# TD_0002-100_2.net
KiCad netlist of a schematic drawn in Altium Designer
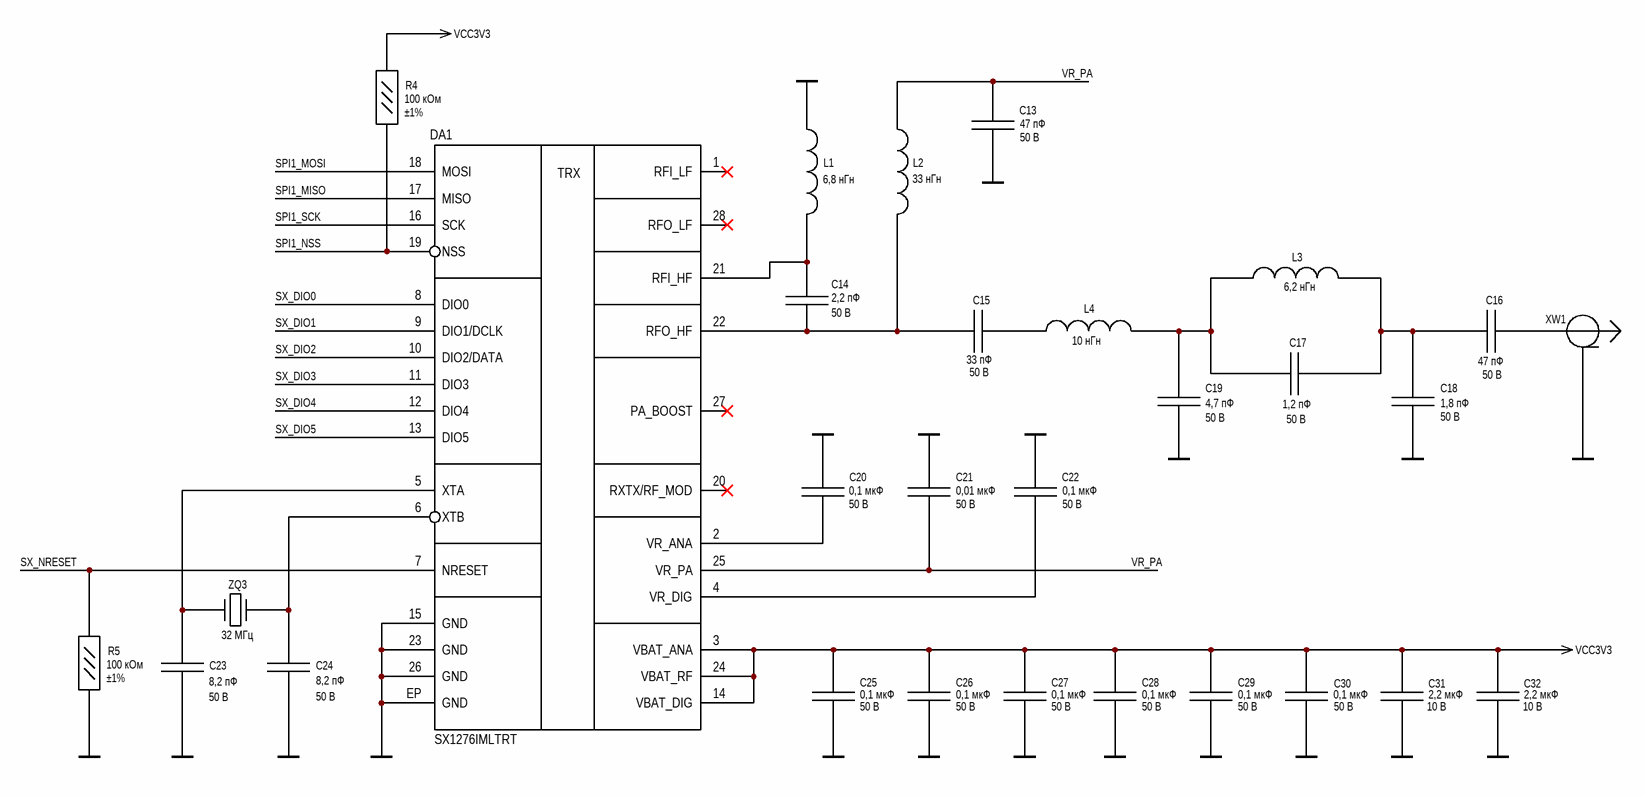
[diagram p0: TD.0002-100_2.SchDoc]

(export (version "E")
  (design (tool "Eeschema 10.0.6"))
  (components
    (comp (ref "C13")
      (value "47 пФ")
      (footprint "C_0402")
      (description "Chip Multilayer Ceramic Capacitor")
      (fields
        (field (name "PART NUMBER") "GRM1555C1H470GA01")
        (field (name "MANUFACTURER") "Murata")
        (field (name "VOLTAGE") "50 В")
      )
      (libsource (lib "Database_Libs") (part "Capacitor"))
    )
    (comp (ref "C14")
      (value "2,2 пФ")
      (footprint "C_0402")
      (description "Chip Multilayer Ceramic Capacitor")
      (fields
        (field (name "PART NUMBER") "GRM1555C1H2R2CA01")
        (field (name "MANUFACTURER") "Murata")
        (field (name "VOLTAGE") "50 В")
      )
      (libsource (lib "Database_Libs") (part "Capacitor"))
    )
    (comp (ref "C15")
      (value "33 пФ")
      (footprint "C_0402")
      (description "Chip Multilayer Ceramic Capacitor")
      (fields
        (field (name "PART NUMBER") "GRM1555C1H330GA01")
        (field (name "MANUFACTURER") "Murata")
        (field (name "VOLTAGE") "50 В")
      )
      (libsource (lib "Database_Libs") (part "Capacitor"))
    )
    (comp (ref "C16")
      (value "47 пФ")
      (footprint "C_0402")
      (description "Chip Multilayer Ceramic Capacitor")
      (fields
        (field (name "PART NUMBER") "GRM1555C1H470GA01")
        (field (name "MANUFACTURER") "Murata")
        (field (name "VOLTAGE") "50 В")
      )
      (libsource (lib "Database_Libs") (part "Capacitor"))
    )
    (comp (ref "C17")
      (value "1,2 пФ")
      (footprint "C_0402")
      (description "Chip Multilayer Ceramic Capacitor")
      (fields
        (field (name "PART NUMBER") "GRM1555C1H1R2CA01")
        (field (name "MANUFACTURER") "Murata")
        (field (name "VOLTAGE") "50 В")
      )
      (libsource (lib "Database_Libs") (part "Capacitor"))
    )
    (comp (ref "C18")
      (value "1,8 пФ")
      (footprint "C_0402")
      (description "Chip Multilayer Ceramic Capacitor")
      (fields
        (field (name "PART NUMBER") "GRM1555C1H1R8CA01")
        (field (name "MANUFACTURER") "Murata")
        (field (name "VOLTAGE") "50 В")
      )
      (libsource (lib "Database_Libs") (part "Capacitor"))
    )
    (comp (ref "C19")
      (value "4,7 пФ")
      (footprint "C_0402")
      (description "Chip Multilayer Ceramic Capacitor")
      (fields
        (field (name "PART NUMBER") "GRM1555C1H4R7CA01")
        (field (name "MANUFACTURER") "Murata")
        (field (name "VOLTAGE") "50 В")
      )
      (libsource (lib "Database_Libs") (part "Capacitor"))
    )
    (comp (ref "C20")
      (value "0,1 мкФ")
      (footprint "C_0402")
      (description "Chip Multilayer Ceramic Capacitor")
      (fields
        (field (name "PART NUMBER") "GRM155R71H104KE14")
        (field (name "MANUFACTURER") "Murata")
        (field (name "VOLTAGE") "50 В")
      )
      (libsource (lib "Database_Libs") (part "Capacitor"))
    )
    (comp (ref "C21")
      (value "0,01 мкФ")
      (footprint "C_0402")
      (description "Chip Multilayer Ceramic Capacitor")
      (fields
        (field (name "PART NUMBER") "GRM155R71H103KA88")
        (field (name "MANUFACTURER") "Murata")
        (field (name "VOLTAGE") "50 В")
      )
      (libsource (lib "Database_Libs") (part "Capacitor"))
    )
    (comp (ref "C22")
      (value "0,1 мкФ")
      (footprint "C_0402")
      (description "Chip Multilayer Ceramic Capacitor")
      (fields
        (field (name "PART NUMBER") "GRM155R71H104KE14")
        (field (name "MANUFACTURER") "Murata")
        (field (name "VOLTAGE") "50 В")
      )
      (libsource (lib "Database_Libs") (part "Capacitor"))
    )
    (comp (ref "C23")
      (value "8,2 пФ")
      (footprint "C_0402")
      (description "Chip Multilayer Ceramic Capacitor")
      (fields
        (field (name "PART NUMBER") "GRM1555C1H8R2WA01")
        (field (name "MANUFACTURER") "Murata")
        (field (name "VOLTAGE") "50 В")
      )
      (libsource (lib "Database_Libs") (part "Capacitor"))
    )
    (comp (ref "C24")
      (value "8,2 пФ")
      (footprint "C_0402")
      (description "Chip Multilayer Ceramic Capacitor")
      (fields
        (field (name "PART NUMBER") "GRM1555C1H8R2WA01")
        (field (name "MANUFACTURER") "Murata")
        (field (name "VOLTAGE") "50 В")
      )
      (libsource (lib "Database_Libs") (part "Capacitor"))
    )
    (comp (ref "C25")
      (value "0,1 мкФ")
      (footprint "C_0402")
      (description "Chip Multilayer Ceramic Capacitor")
      (fields
        (field (name "PART NUMBER") "GRM155R71H104KE14")
        (field (name "MANUFACTURER") "Murata")
        (field (name "VOLTAGE") "50 В")
      )
      (libsource (lib "Database_Libs") (part "Capacitor"))
    )
    (comp (ref "C26")
      (value "0,1 мкФ")
      (footprint "C_0402")
      (description "Chip Multilayer Ceramic Capacitor")
      (fields
        (field (name "PART NUMBER") "GRM155R71H104KE14")
        (field (name "MANUFACTURER") "Murata")
        (field (name "VOLTAGE") "50 В")
      )
      (libsource (lib "Database_Libs") (part "Capacitor"))
    )
    (comp (ref "C27")
      (value "0,1 мкФ")
      (footprint "C_0402")
      (description "Chip Multilayer Ceramic Capacitor")
      (fields
        (field (name "PART NUMBER") "GRM155R71H104KE14")
        (field (name "MANUFACTURER") "Murata")
        (field (name "VOLTAGE") "50 В")
      )
      (libsource (lib "Database_Libs") (part "Capacitor"))
    )
    (comp (ref "C28")
      (value "0,1 мкФ")
      (footprint "C_0402")
      (description "Chip Multilayer Ceramic Capacitor")
      (fields
        (field (name "PART NUMBER") "GRM155R71H104KE14")
        (field (name "MANUFACTURER") "Murata")
        (field (name "VOLTAGE") "50 В")
      )
      (libsource (lib "Database_Libs") (part "Capacitor"))
    )
    (comp (ref "C29")
      (value "0,1 мкФ")
      (footprint "C_0402")
      (description "Chip Multilayer Ceramic Capacitor")
      (fields
        (field (name "PART NUMBER") "GRM155R71H104KE14")
        (field (name "MANUFACTURER") "Murata")
        (field (name "VOLTAGE") "50 В")
      )
      (libsource (lib "Database_Libs") (part "Capacitor"))
    )
    (comp (ref "C30")
      (value "0,1 мкФ")
      (footprint "C_0402")
      (description "Chip Multilayer Ceramic Capacitor")
      (fields
        (field (name "PART NUMBER") "GRM155R71H104KE14")
        (field (name "MANUFACTURER") "Murata")
        (field (name "VOLTAGE") "50 В")
      )
      (libsource (lib "Database_Libs") (part "Capacitor"))
    )
    (comp (ref "C31")
      (value "2,2 мкФ")
      (footprint "C_0402")
      (description "Chip Multilayer Ceramic Capacitor")
      (fields
        (field (name "PART NUMBER") "GRM155C81A225ME44")
        (field (name "MANUFACTURER") "Murata")
        (field (name "VOLTAGE") "10 В")
      )
      (libsource (lib "Database_Libs") (part "Capacitor"))
    )
    (comp (ref "C32")
      (value "2,2 мкФ")
      (footprint "C_0402")
      (description "Chip Multilayer Ceramic Capacitor")
      (fields
        (field (name "PART NUMBER") "GRM155C81A225ME44")
        (field (name "MANUFACTURER") "Murata")
        (field (name "VOLTAGE") "10 В")
      )
      (libsource (lib "Database_Libs") (part "Capacitor"))
    )
    (comp (ref "DA1")
      (value "SX1276IMLTRT")
      (footprint "FirstLib:QFN_28")
      (description "860 MHz to 1020 MHz Low Power Long Range Transceiver")
      (fields (field (name "MANUFACTURER") "Semtech"))
      (libsource (lib "FirstLib") (part "SX1276IMLTRT"))
    )
    (comp (ref "L1")
      (value "6,8 нГн")
      (footprint "L_0402")
      (fields
        (field (name "PART NUMBER") "LQW15AN6N8G80")
        (field (name "TOLERANCE") "±2%")
        (field (name "MANUFACTURER") "Murata")
      )
      (libsource (lib "Database_Libs") (part "Inductor"))
    )
    (comp (ref "L2")
      (value "33 нГн")
      (footprint "L_0402")
      (fields
        (field (name "PART NUMBER") "LQW15AN33NJ00")
        (field (name "TOLERANCE") "±5%")
        (field (name "MANUFACTURER") "Murata")
      )
      (libsource (lib "Database_Libs") (part "Inductor"))
    )
    (comp (ref "L3")
      (value "6,2 нГн")
      (footprint "L_0402")
      (fields
        (field (name "PART NUMBER") "LQW15AN6N2G8Z")
        (field (name "TOLERANCE") "±2%")
        (field (name "MANUFACTURER") "Murata")
      )
      (libsource (lib "Database_Libs") (part "Inductor"))
    )
    (comp (ref "L4")
      (value "10 нГн")
      (footprint "L_0402")
      (fields
        (field (name "PART NUMBER") "LQW15AN10NG80")
        (field (name "TOLERANCE") "±2%")
        (field (name "MANUFACTURER") "Murata")
      )
      (libsource (lib "Database_Libs") (part "Inductor"))
    )
    (comp (ref "R4")
      (value "100 кОм")
      (footprint "R_0402")
      (description "High Reliability")
      (fields
        (field (name "ACCURACY") "±1%")
        (field (name "PART NUMBER") "RC0402FR-07100KL")
        (field (name "VOLTAGE") "50 В")
      )
      (libsource (lib "Database_Libs") (part "Resistor_0.05W"))
    )
    (comp (ref "R5")
      (value "100 кОм")
      (footprint "R_0402")
      (description "High Reliability")
      (fields
        (field (name "ACCURACY") "±1%")
        (field (name "PART NUMBER") "RC0402FR-07100KL")
        (field (name "VOLTAGE") "50 В")
      )
      (libsource (lib "Database_Libs") (part "Resistor_0.05W"))
    )
    (comp (ref "XW1")
      (value "U.FL-R-SMT")
      (footprint "FirstLib:U.FL-R-SMT")
      (fields (field (name "MANUFACTURER") "Hirose Electric"))
      (libsource (lib "FirstLib") (part "U.FL-R-SMT"))
    )
    (comp (ref "ZQ3")
      (value "32 МГц")
      (footprint "FirstLib:CM9V-T1A")
      (fields (field (name "Comment") "Quartz"))
      (libsource (lib "FirstLib") (part "Quartz"))
    )
  )
  (nets
    (net (code "1") (name "/SPI1_MISO") (class "Default")
      (node (ref "DA1") (pin "17") (pinfunction "MISO_17") (pintype "passive"))
    )
    (net (code "2") (name "/SPI1_MOSI") (class "Default")
      (node (ref "DA1") (pin "18") (pinfunction "MOSI_18") (pintype "passive"))
    )
    (net (code "3") (name "/SPI1_NSS") (class "Default")
      (node (ref "DA1") (pin "19") (pinfunction "NSS_19") (pintype "passive"))
      (node (ref "R4") (pin "1") (pinfunction "1_1") (pintype "passive"))
    )
    (net (code "4") (name "/SPI1_SCK") (class "Default")
      (node (ref "DA1") (pin "16") (pinfunction "SCK_16") (pintype "passive"))
    )
    (net (code "5") (name "/SX_DIO0") (class "Default")
      (node (ref "DA1") (pin "8") (pinfunction "DIO0_8") (pintype "passive"))
    )
    (net (code "6") (name "/SX_DIO1") (class "Default")
      (node (ref "DA1") (pin "9") (pinfunction "DIO1/DCLK_9") (pintype "passive"))
    )
    (net (code "7") (name "/SX_DIO2") (class "Default")
      (node (ref "DA1") (pin "10") (pinfunction "DIO2/DATA_10") (pintype "passive"))
    )
    (net (code "8") (name "/SX_DIO3") (class "Default")
      (node (ref "DA1") (pin "11") (pinfunction "DIO3_11") (pintype "passive"))
    )
    (net (code "9") (name "/SX_DIO4") (class "Default")
      (node (ref "DA1") (pin "12") (pinfunction "DIO4_12") (pintype "passive"))
    )
    (net (code "10") (name "/SX_DIO5") (class "Default")
      (node (ref "DA1") (pin "13") (pinfunction "DIO5_13") (pintype "passive"))
    )
    (net (code "11") (name "/SX_NRESET") (class "Default")
      (node (ref "DA1") (pin "7") (pinfunction "NRESET_7") (pintype "passive"))
      (node (ref "R5") (pin "2") (pinfunction "2_2") (pintype "passive"))
    )
    (net (code "12") (name "/VR_PA") (class "Default")
      (node (ref "C13") (pin "1") (pinfunction "1_1") (pintype "passive"))
      (node (ref "C21") (pin "2") (pinfunction "2_2") (pintype "passive"))
      (node (ref "DA1") (pin "25") (pinfunction "VR_PA_25") (pintype "passive"))
      (node (ref "L2") (pin "1") (pinfunction "1_1") (pintype "passive"))
    )
    (net (code "13") (name "GND") (class "Default")
      (node (ref "C13") (pin "2") (pinfunction "2_2") (pintype "passive"))
      (node (ref "C18") (pin "2") (pinfunction "2_2") (pintype "passive"))
      (node (ref "C19") (pin "2") (pinfunction "2_2") (pintype "passive"))
      (node (ref "C20") (pin "1") (pinfunction "1_1") (pintype "passive"))
      (node (ref "C21") (pin "1") (pinfunction "1_1") (pintype "passive"))
      (node (ref "C22") (pin "1") (pinfunction "1_1") (pintype "passive"))
      (node (ref "C23") (pin "2") (pinfunction "2_2") (pintype "passive"))
      (node (ref "C24") (pin "2") (pinfunction "2_2") (pintype "passive"))
      (node (ref "C25") (pin "2") (pinfunction "2_2") (pintype "passive"))
      (node (ref "C26") (pin "2") (pinfunction "2_2") (pintype "passive"))
      (node (ref "C27") (pin "2") (pinfunction "2_2") (pintype "passive"))
      (node (ref "C28") (pin "2") (pinfunction "2_2") (pintype "passive"))
      (node (ref "C29") (pin "2") (pinfunction "2_2") (pintype "passive"))
      (node (ref "C30") (pin "2") (pinfunction "2_2") (pintype "passive"))
      (node (ref "C31") (pin "2") (pinfunction "2_2") (pintype "passive"))
      (node (ref "C32") (pin "2") (pinfunction "2_2") (pintype "passive"))
      (node (ref "DA1") (pin "15") (pinfunction "GND_15") (pintype "passive"))
      (node (ref "DA1") (pin "23") (pinfunction "GND_23") (pintype "passive"))
      (node (ref "DA1") (pin "26") (pinfunction "GND_26") (pintype "passive"))
      (node (ref "DA1") (pin "EP") (pinfunction "GND_EP") (pintype "passive"))
      (node (ref "L1") (pin "1") (pinfunction "1_1") (pintype "passive"))
      (node (ref "R5") (pin "1") (pinfunction "1_1") (pintype "passive"))
      (node (ref "XW1") (pin "2") (pinfunction "GND_2") (pintype "passive"))
    )
    (net (code "14") (name "Net-(C15-Pad2)") (class "Default")
      (node (ref "C15") (pin "2") (pinfunction "2_2") (pintype "passive"))
      (node (ref "L4") (pin "1") (pinfunction "1_1") (pintype "passive"))
    )
    (net (code "15") (name "Net-(C16-Pad1)") (class "Default")
      (node (ref "C16") (pin "1") (pinfunction "1_1") (pintype "passive"))
      (node (ref "C17") (pin "2") (pinfunction "2_2") (pintype "passive"))
      (node (ref "C18") (pin "1") (pinfunction "1_1") (pintype "passive"))
      (node (ref "L3") (pin "2") (pinfunction "2_2") (pintype "passive"))
    )
    (net (code "16") (name "Net-(C17-Pad1)") (class "Default")
      (node (ref "C17") (pin "1") (pinfunction "1_1") (pintype "passive"))
      (node (ref "C19") (pin "1") (pinfunction "1_1") (pintype "passive"))
      (node (ref "L3") (pin "1") (pinfunction "1_1") (pintype "passive"))
      (node (ref "L4") (pin "2") (pinfunction "2_2") (pintype "passive"))
    )
    (net (code "17") (name "Net-(DA1-RFI_HF)") (class "Default")
      (node (ref "C14") (pin "1") (pinfunction "1_1") (pintype "passive"))
      (node (ref "DA1") (pin "21") (pinfunction "RFI_HF_21") (pintype "passive"))
      (node (ref "L1") (pin "2") (pinfunction "2_2") (pintype "passive"))
    )
    (net (code "18") (name "Net-(DA1-RFO_HF)") (class "Default")
      (node (ref "C14") (pin "2") (pinfunction "2_2") (pintype "passive"))
      (node (ref "C15") (pin "1") (pinfunction "1_1") (pintype "passive"))
      (node (ref "DA1") (pin "22") (pinfunction "RFO_HF_22") (pintype "passive"))
      (node (ref "L2") (pin "2") (pinfunction "2_2") (pintype "passive"))
    )
    (net (code "19") (name "Net-(DA1-VR_ANA)") (class "Default")
      (node (ref "C20") (pin "2") (pinfunction "2_2") (pintype "passive"))
      (node (ref "DA1") (pin "2") (pinfunction "VR_ANA_2") (pintype "passive"))
    )
    (net (code "20") (name "Net-(DA1-VR_DIG)") (class "Default")
      (node (ref "C22") (pin "2") (pinfunction "2_2") (pintype "passive"))
      (node (ref "DA1") (pin "4") (pinfunction "VR_DIG_4") (pintype "passive"))
    )
    (net (code "21") (name "Net-(DA1-XTA)") (class "Default")
      (node (ref "C23") (pin "1") (pinfunction "1_1") (pintype "passive"))
      (node (ref "DA1") (pin "5") (pinfunction "XTA_5") (pintype "passive"))
      (node (ref "ZQ3") (pin "1") (pinfunction "XI_1") (pintype "passive"))
    )
    (net (code "22") (name "Net-(DA1-XTB)") (class "Default")
      (node (ref "C24") (pin "1") (pinfunction "1_1") (pintype "passive"))
      (node (ref "DA1") (pin "6") (pinfunction "XTB_6") (pintype "passive"))
      (node (ref "ZQ3") (pin "2") (pinfunction "XO_2") (pintype "passive"))
    )
    (net (code "23") (name "Net-(XW1-SIGNAL)") (class "Default")
      (node (ref "C16") (pin "2") (pinfunction "2_2") (pintype "passive"))
      (node (ref "XW1") (pin "1") (pinfunction "SIGNAL_1") (pintype "passive"))
    )
    (net (code "24") (name "VCC3V3") (class "Default")
      (node (ref "C25") (pin "1") (pinfunction "1_1") (pintype "passive"))
      (node (ref "C26") (pin "1") (pinfunction "1_1") (pintype "passive"))
      (node (ref "C27") (pin "1") (pinfunction "1_1") (pintype "passive"))
      (node (ref "C28") (pin "1") (pinfunction "1_1") (pintype "passive"))
      (node (ref "C29") (pin "1") (pinfunction "1_1") (pintype "passive"))
      (node (ref "C30") (pin "1") (pinfunction "1_1") (pintype "passive"))
      (node (ref "C31") (pin "1") (pinfunction "1_1") (pintype "passive"))
      (node (ref "C32") (pin "1") (pinfunction "1_1") (pintype "passive"))
      (node (ref "DA1") (pin "14") (pinfunction "VBAT_DIG_14") (pintype "passive"))
      (node (ref "DA1") (pin "24") (pinfunction "VBAT_RF_24") (pintype "passive"))
      (node (ref "DA1") (pin "3") (pinfunction "VBAT_ANA_3") (pintype "passive"))
      (node (ref "R4") (pin "2") (pinfunction "2_2") (pintype "passive"))
    )
    (net (code "25") (name "unconnected-(DA1-PA_BOOST-Pad27)") (class "Default")
      (node (ref "DA1") (pin "27") (pinfunction "PA_BOOST_27") (pintype "passive+no_connect"))
    )
    (net (code "26") (name "unconnected-(DA1-RFI_LF-Pad1)") (class "Default")
      (node (ref "DA1") (pin "1") (pinfunction "RFI_LF_1") (pintype "passive+no_connect"))
    )
    (net (code "27") (name "unconnected-(DA1-RFO_LF-Pad28)") (class "Default")
      (node (ref "DA1") (pin "28") (pinfunction "RFO_LF_28") (pintype "passive+no_connect"))
    )
    (net (code "28") (name "unconnected-(DA1-RXTX{slash}RF_MOD-Pad20)") (class "Default")
      (node (ref "DA1") (pin "20") (pinfunction "RXTX/RF_MOD_20") (pintype "passive+no_connect"))
    )
  )
)
